# light-meter-B.net
KiCad netlist of a schematic drawn in EAGLE
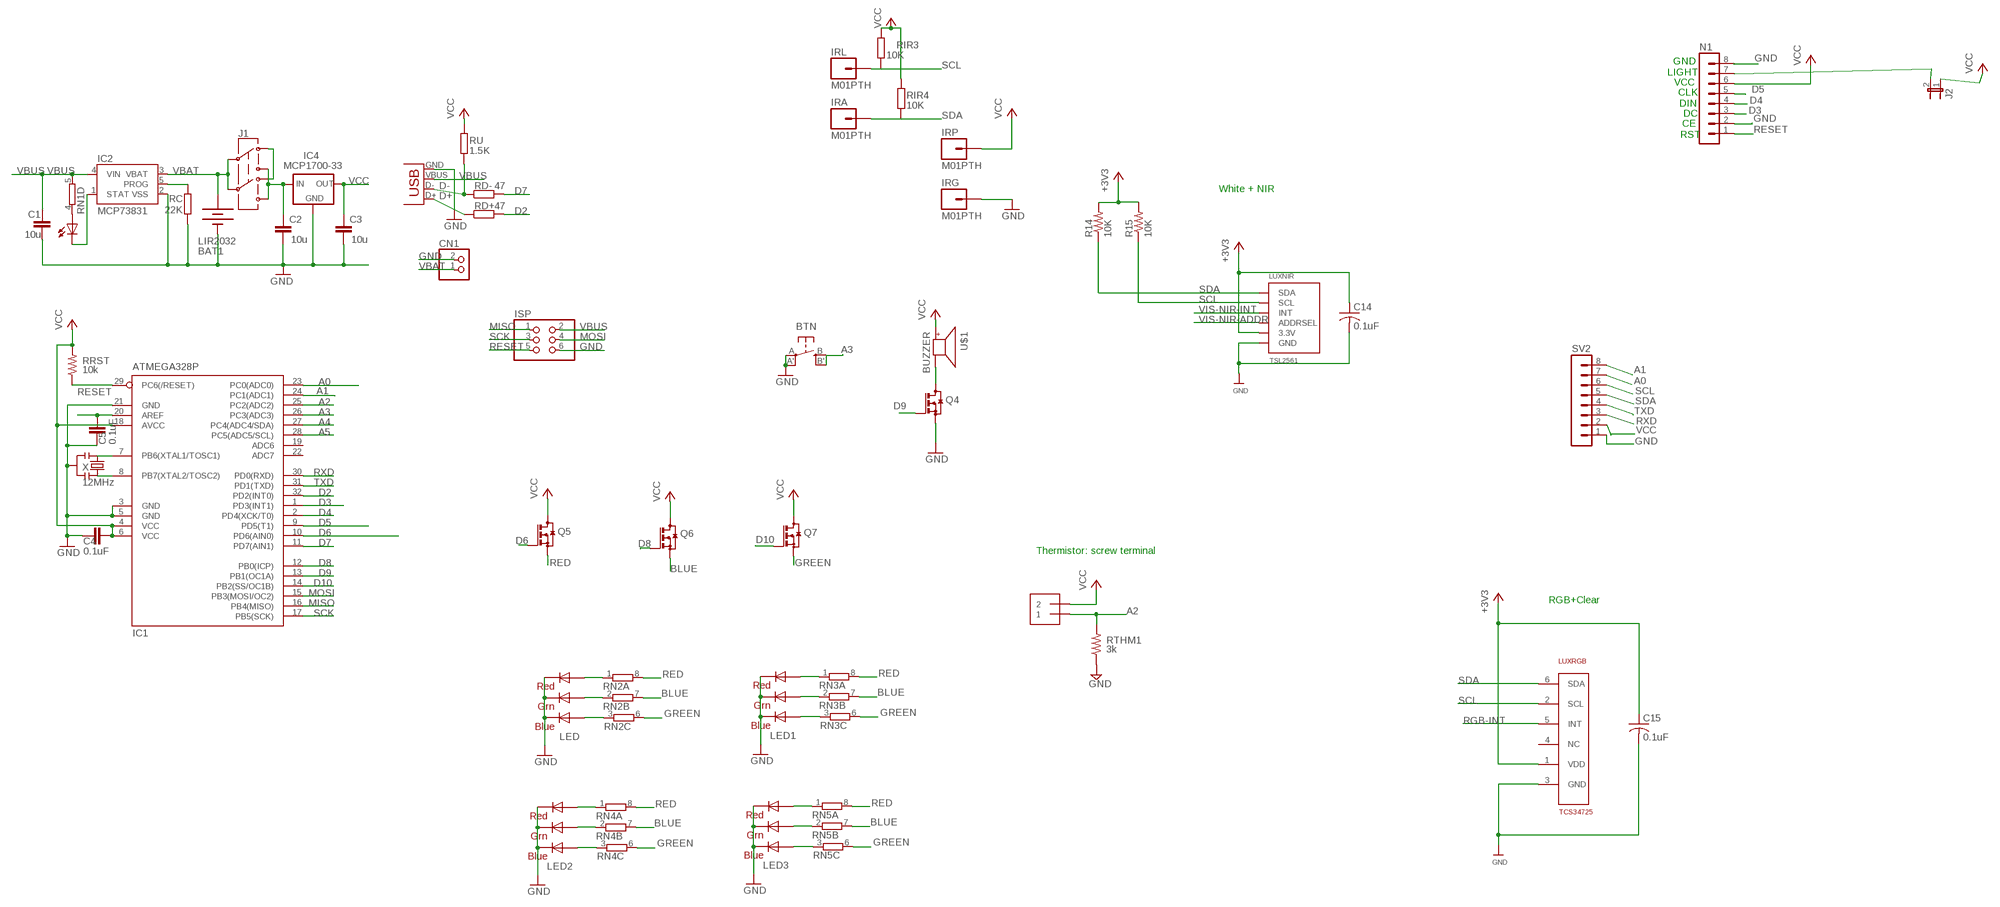
[diagram p0: schematic, sheet 1]

(export (version "E")
  (design (tool "Eeschema 10.0.6"))
  (components
    (comp (ref "BAT1")
      (value "LIR2032")
      (footprint "eagle-import:BATTCOM_20MM_PTH_SMT")
      (libsource (lib "eagle-import") (part "BATTERYBATTCOM_20MM_PTH_SMT"))
    )
    (comp (ref "BTN")
      (value "EVQQ2")
      (footprint "eagle-import:EVQ-Q2")
      (libsource (lib "eagle-import") (part "EVQQ2"))
    )
    (comp (ref "C1")
      (value "10u")
      (footprint "eagle-import:C0805")
      (libsource (lib "eagle-import") (part "resistor_C-EUC0805"))
    )
    (comp (ref "C2")
      (value "10u")
      (footprint "eagle-import:C0805")
      (libsource (lib "eagle-import") (part "resistor_C-EUC0805"))
    )
    (comp (ref "C3")
      (value "10u")
      (footprint "eagle-import:C0805")
      (libsource (lib "eagle-import") (part "resistor_C-EUC0805"))
    )
    (comp (ref "C4")
      (value "0.1uF")
      (footprint "eagle-import:C0805")
      (libsource (lib "eagle-import") (part "C-EUC0805"))
    )
    (comp (ref "C5")
      (value "0.1uF")
      (footprint "eagle-import:C0805")
      (libsource (lib "eagle-import") (part "C-EUC0805"))
    )
    (comp (ref "C14")
      (value "0.1uF")
      (footprint "eagle-import:C0805")
      (libsource (lib "eagle-import") (part "C-USC0805"))
    )
    (comp (ref "C15")
      (value "0.1uF")
      (footprint "eagle-import:C0805")
      (libsource (lib "eagle-import") (part "C-USC0805"))
    )
    (comp (ref "CHG")
      (value "0805")
      (footprint "eagle-import:CHIPLED_0805")
      (libsource (lib "eagle-import") (part "LEDCHIPLED_0805"))
    )
    (comp (ref "CN1")
      (value "JST_2PIN-SMT-RA")
      (footprint "eagle-import:JST-PH-2-SMT-RA")
      (libsource (lib "eagle-import") (part "JST_2PIN-SMT-RA"))
    )
    (comp (ref "IC1")
      (value "ATMEGA328P")
      (footprint "eagle-import:TQFP32-08")
      (fields (field (name "MPN") "ATMEGA8-16AU"))
      (libsource (lib "eagle-import") (part "MEGA8-AI"))
    )
    (comp (ref "IC2")
      (value "MCP73831")
      (footprint "eagle-import:SOT23-5")
      (libsource (lib "eagle-import") (part "MCP73831"))
    )
    (comp (ref "IC4")
      (value "MCP1700-33")
      (footprint "eagle-import:SOT23")
      (libsource (lib "eagle-import") (part "MCP1700SOT233"))
    )
    (comp (ref "IRA")
      (value "M01PTH")
      (footprint "eagle-import:1X01")
      (libsource (lib "eagle-import") (part "M01PTH"))
    )
    (comp (ref "IRG")
      (value "M01PTH")
      (footprint "eagle-import:1X01")
      (libsource (lib "eagle-import") (part "M01PTH"))
    )
    (comp (ref "IRL")
      (value "M01PTH")
      (footprint "eagle-import:1X01")
      (libsource (lib "eagle-import") (part "M01PTH"))
    )
    (comp (ref "IRP")
      (value "M01PTH")
      (footprint "eagle-import:1X01")
      (libsource (lib "eagle-import") (part "M01PTH"))
    )
    (comp (ref "ISP")
      (value "PINHD-2X3")
      (footprint "eagle-import:2X03")
      (libsource (lib "eagle-import") (part "PINHD-2X3"))
    )
    (comp (ref "J1")
      (value "AYZ0202")
      (footprint "eagle-import:AYZ0202")
      (libsource (lib "eagle-import") (part "AYZ0202"))
    )
    (comp (ref "J2")
      (value "JP1E")
      (footprint "eagle-import:JP1")
      (libsource (lib "eagle-import") (part "JP1E"))
    )
    (comp (ref "LED")
      (value "RGBLED5050")
      (footprint "eagle-import:RGBLED5050")
      (libsource (lib "eagle-import") (part "RGBLED5050"))
    )
    (comp (ref "LED1")
      (value "RGBLED5050")
      (footprint "eagle-import:RGBLED5050")
      (libsource (lib "eagle-import") (part "RGBLED5050"))
    )
    (comp (ref "LED2")
      (value "RGBLED5050")
      (footprint "eagle-import:RGBLED5050")
      (libsource (lib "eagle-import") (part "RGBLED5050"))
    )
    (comp (ref "LED3")
      (value "RGBLED5050")
      (footprint "eagle-import:RGBLED5050")
      (libsource (lib "eagle-import") (part "RGBLED5050"))
    )
    (comp (ref "LUXNIR")
      (value "TSL2561")
      (footprint "eagle-import:TSL2561_FN@1")
      (libsource (lib "eagle-import") (part "TSL2561"))
    )
    (comp (ref "LUXRGB")
      (value "TCS34725")
      (footprint "eagle-import:DFN-6")
      (libsource (lib "eagle-import") (part "TCS34725"))
    )
    (comp (ref "N1")
      (value "MA08-1")
      (footprint "eagle-import:MA08-1")
      (libsource (lib "eagle-import") (part "MA08-1"))
    )
    (comp (ref "Q4")
      (value "BSS123")
      (footprint "eagle-import:SOT23")
      (libsource (lib "eagle-import") (part "BSS123"))
    )
    (comp (ref "Q5")
      (value "BSS123")
      (footprint "eagle-import:SOT23")
      (libsource (lib "eagle-import") (part "BSS123"))
    )
    (comp (ref "Q6")
      (value "BSS123")
      (footprint "eagle-import:SOT23")
      (libsource (lib "eagle-import") (part "BSS123"))
    )
    (comp (ref "Q7")
      (value "BSS123")
      (footprint "eagle-import:SOT23")
      (libsource (lib "eagle-import") (part "BSS123"))
    )
    (comp (ref "R14")
      (value "10K")
      (footprint "eagle-import:R0805")
      (libsource (lib "eagle-import") (part "R-US_R0805"))
    )
    (comp (ref "R15")
      (value "10K")
      (footprint "eagle-import:R0805")
      (libsource (lib "eagle-import") (part "R-US_R0805"))
    )
    (comp (ref "RC")
      (value "22K")
      (footprint "eagle-import:R0805")
      (libsource (lib "eagle-import") (part "R-EU_R0805"))
    )
    (comp (ref "RD+")
      (value "47")
      (footprint "eagle-import:R0805")
      (libsource (lib "eagle-import") (part "R-EU_R0805"))
    )
    (comp (ref "RD-")
      (value "47")
      (footprint "eagle-import:R0805")
      (libsource (lib "eagle-import") (part "R-EU_R0805"))
    )
    (comp (ref "RIR3")
      (value "10K")
      (footprint "eagle-import:R0805")
      (libsource (lib "eagle-import") (part "R-EU_R0805"))
    )
    (comp (ref "RIR4")
      (value "10K")
      (footprint "eagle-import:R0805")
      (libsource (lib "eagle-import") (part "R-EU_R0805"))
    )
    (comp (ref "RN1")
      (value "4R-NEXB38V")
      (footprint "eagle-import:EXB38V")
      (libsource (lib "eagle-import") (part "4R-NEXB38V"))
    )
    (comp (ref "RN2")
      (value "4R-NEXB38V")
      (footprint "eagle-import:EXB38V")
      (libsource (lib "eagle-import") (part "4R-NEXB38V"))
    )
    (comp (ref "RN3")
      (value "4R-NEXB38V")
      (footprint "eagle-import:EXB38V")
      (libsource (lib "eagle-import") (part "4R-NEXB38V"))
    )
    (comp (ref "RN4")
      (value "4R-NEXB38V")
      (footprint "eagle-import:EXB38V")
      (libsource (lib "eagle-import") (part "4R-NEXB38V"))
    )
    (comp (ref "RN5")
      (value "4R-NEXB38V")
      (footprint "eagle-import:EXB38V")
      (libsource (lib "eagle-import") (part "4R-NEXB38V"))
    )
    (comp (ref "RRST")
      (value "10k")
      (footprint "eagle-import:R0805@1")
      (libsource (lib "eagle-import") (part "rcl_R-US_R0805"))
    )
    (comp (ref "RTHM1")
      (value "3k")
      (footprint "eagle-import:R0805@1")
      (libsource (lib "eagle-import") (part "rcl_R-US_R0805"))
    )
    (comp (ref "RU")
      (value "1.5K")
      (footprint "eagle-import:R0805")
      (libsource (lib "eagle-import") (part "R-EU_R0805"))
    )
    (comp (ref "SV2")
      (value "MA08-1")
      (footprint "eagle-import:MA08-1")
      (libsource (lib "eagle-import") (part "MA08-1"))
    )
    (comp (ref "THM1")
      (value "1X2-3.5MM")
      (footprint "eagle-import:1X2-3.5MM")
      (libsource (lib "eagle-import") (part "1X2-3.5MM"))
    )
    (comp (ref "U$1")
      (value "BUZZER")
      (footprint "eagle-import:SMT-8585-BUZZER")
      (libsource (lib "eagle-import") (part "BUZZER"))
    )
    (comp (ref "X")
      (value "12MHz")
      (footprint "eagle-import:RESONATOR-SMD")
      (libsource (lib "eagle-import") (part "RESONATORSMD"))
    )
    (comp (ref "X1")
      (value "USBSMD")
      (footprint "eagle-import:USB-MINIB")
      (libsource (lib "eagle-import") (part "USBSMD"))
    )
  )
  (nets
    (net (code "1") (name "+3V3") (class "Default")
      (node (ref "C14") (pin "1") (pinfunction "1_1") (pintype "passive"))
      (node (ref "C15") (pin "1") (pinfunction "1_1") (pintype "passive"))
      (node (ref "LUXNIR") (pin "VDD") (pinfunction "3.3V_VDD") (pintype "bidirectional"))
      (node (ref "LUXRGB") (pin "1") (pinfunction "VDD_1") (pintype "bidirectional"))
      (node (ref "R14") (pin "2") (pinfunction "2_2") (pintype "passive"))
      (node (ref "R15") (pin "2") (pinfunction "2_2") (pintype "passive"))
    )
    (net (code "2") (name "/A0") (class "Default")
      (node (ref "IC1") (pin "23") (pinfunction "PC0(ADC0)_23") (pintype "bidirectional"))
      (node (ref "SV2") (pin "7") (pinfunction "7_7") (pintype "passive"))
    )
    (net (code "3") (name "/A1") (class "Default")
      (node (ref "IC1") (pin "24") (pinfunction "PC1(ADC1)_24") (pintype "bidirectional"))
      (node (ref "SV2") (pin "8") (pinfunction "8_8") (pintype "passive"))
    )
    (net (code "4") (name "/A2") (class "Default")
      (node (ref "IC1") (pin "25") (pinfunction "PC2(ADC2)_25") (pintype "bidirectional"))
      (node (ref "RTHM1") (pin "2") (pinfunction "2_2") (pintype "passive"))
      (node (ref "THM1") (pin "1") (pinfunction "1_1") (pintype "passive"))
    )
    (net (code "5") (name "/A3") (class "Default")
      (node (ref "BTN") (pin "B") (pinfunction "S_B") (pintype "passive"))
      (node (ref "BTN") (pin "B'") (pinfunction "S1_B'") (pintype "passive"))
      (node (ref "IC1") (pin "26") (pinfunction "PC3(ADC3)_26") (pintype "bidirectional"))
    )
    (net (code "6") (name "/A4") (class "Default")
      (node (ref "IC1") (pin "27") (pinfunction "PC4(ADC4/SDA)_27") (pintype "bidirectional"))
    )
    (net (code "7") (name "/A5") (class "Default")
      (node (ref "IC1") (pin "28") (pinfunction "PC5(ADC5/SCL)_28") (pintype "bidirectional"))
    )
    (net (code "8") (name "/BLUE") (class "Default")
      (node (ref "Q6") (pin "2") (pinfunction "S_2") (pintype "passive"))
      (node (ref "RN2") (pin "7") (pinfunction "2_7") (pintype "passive"))
      (node (ref "RN3") (pin "7") (pinfunction "2_7") (pintype "passive"))
      (node (ref "RN4") (pin "7") (pinfunction "2_7") (pintype "passive"))
      (node (ref "RN5") (pin "7") (pinfunction "2_7") (pintype "passive"))
    )
    (net (code "9") (name "/D+") (class "Default")
      (node (ref "RD+") (pin "1") (pinfunction "1_1") (pintype "passive"))
      (node (ref "X1") (pin "D+") (pinfunction "D+_D+") (pintype "bidirectional"))
    )
    (net (code "10") (name "/D-") (class "Default")
      (node (ref "RD-") (pin "1") (pinfunction "1_1") (pintype "passive"))
      (node (ref "RU") (pin "1") (pinfunction "1_1") (pintype "passive"))
      (node (ref "X1") (pin "D-") (pinfunction "D-_D-") (pintype "bidirectional"))
    )
    (net (code "11") (name "/D2") (class "Default")
      (node (ref "IC1") (pin "32") (pinfunction "PD2(INT0)_32") (pintype "bidirectional"))
      (node (ref "RD+") (pin "2") (pinfunction "2_2") (pintype "passive"))
    )
    (net (code "12") (name "/D3") (class "Default")
      (node (ref "IC1") (pin "1") (pinfunction "PD3(INT1)_1") (pintype "bidirectional"))
      (node (ref "N1") (pin "3") (pinfunction "3_3") (pintype "passive"))
    )
    (net (code "13") (name "/D4") (class "Default")
      (node (ref "IC1") (pin "2") (pinfunction "PD4(XCK/T0)_2") (pintype "bidirectional"))
      (node (ref "N1") (pin "4") (pinfunction "4_4") (pintype "passive"))
    )
    (net (code "14") (name "/D5") (class "Default")
      (node (ref "IC1") (pin "9") (pinfunction "PD5(T1)_9") (pintype "bidirectional"))
      (node (ref "N1") (pin "5") (pinfunction "5_5") (pintype "passive"))
    )
    (net (code "15") (name "/D6") (class "Default")
      (node (ref "IC1") (pin "10") (pinfunction "PD6(AIN0)_10") (pintype "bidirectional"))
      (node (ref "Q5") (pin "1") (pinfunction "G_1") (pintype "passive"))
    )
    (net (code "16") (name "/D7") (class "Default")
      (node (ref "IC1") (pin "11") (pinfunction "PD7(AIN1)_11") (pintype "bidirectional"))
      (node (ref "RD-") (pin "2") (pinfunction "2_2") (pintype "passive"))
    )
    (net (code "17") (name "/D8") (class "Default")
      (node (ref "IC1") (pin "12") (pinfunction "PB0(ICP)_12") (pintype "bidirectional"))
      (node (ref "Q6") (pin "1") (pinfunction "G_1") (pintype "passive"))
    )
    (net (code "18") (name "/D9") (class "Default")
      (node (ref "IC1") (pin "13") (pinfunction "PB1(OC1A)_13") (pintype "bidirectional"))
      (node (ref "Q4") (pin "1") (pinfunction "G_1") (pintype "passive"))
    )
    (net (code "19") (name "/D10") (class "Default")
      (node (ref "IC1") (pin "14") (pinfunction "PB2(SS/OC1B)_14") (pintype "bidirectional"))
      (node (ref "Q7") (pin "1") (pinfunction "G_1") (pintype "passive"))
    )
    (net (code "20") (name "/GREEN") (class "Default")
      (node (ref "Q7") (pin "2") (pinfunction "S_2") (pintype "passive"))
      (node (ref "RN2") (pin "6") (pinfunction "2_6") (pintype "passive"))
      (node (ref "RN3") (pin "6") (pinfunction "2_6") (pintype "passive"))
      (node (ref "RN4") (pin "6") (pinfunction "2_6") (pintype "passive"))
      (node (ref "RN5") (pin "6") (pinfunction "2_6") (pintype "passive"))
    )
    (net (code "21") (name "/MISO") (class "Default")
      (node (ref "IC1") (pin "16") (pinfunction "PB4(MISO)_16") (pintype "bidirectional"))
      (node (ref "ISP") (pin "1") (pinfunction "1_1") (pintype "passive"))
    )
    (net (code "22") (name "/MOSI") (class "Default")
      (node (ref "IC1") (pin "15") (pinfunction "PB3(MOSI/OC2)_15") (pintype "bidirectional"))
      (node (ref "ISP") (pin "4") (pinfunction "4_4") (pintype "passive"))
    )
    (net (code "23") (name "/RED") (class "Default")
      (node (ref "Q5") (pin "2") (pinfunction "S_2") (pintype "passive"))
      (node (ref "RN2") (pin "8") (pinfunction "2_8") (pintype "passive"))
      (node (ref "RN3") (pin "8") (pinfunction "2_8") (pintype "passive"))
      (node (ref "RN4") (pin "8") (pinfunction "2_8") (pintype "passive"))
      (node (ref "RN5") (pin "8") (pinfunction "2_8") (pintype "passive"))
    )
    (net (code "24") (name "/RESET") (class "Default")
      (node (ref "IC1") (pin "29") (pinfunction "PC6(/RESET)_29") (pintype "bidirectional"))
      (node (ref "ISP") (pin "5") (pinfunction "5_5") (pintype "passive"))
      (node (ref "N1") (pin "1") (pinfunction "1_1") (pintype "passive"))
      (node (ref "RRST") (pin "1") (pinfunction "1_1") (pintype "passive"))
    )
    (net (code "25") (name "/RGB-INT") (class "Default")
      (node (ref "LUXRGB") (pin "5") (pinfunction "INT_5") (pintype "bidirectional"))
    )
    (net (code "26") (name "/RXD") (class "Default")
      (node (ref "IC1") (pin "30") (pinfunction "PD0(RXD)_30") (pintype "bidirectional"))
      (node (ref "SV2") (pin "3") (pinfunction "3_3") (pintype "passive"))
    )
    (net (code "27") (name "/SCK") (class "Default")
      (node (ref "IC1") (pin "17") (pinfunction "PB5(SCK)_17") (pintype "bidirectional"))
      (node (ref "ISP") (pin "3") (pinfunction "3_3") (pintype "passive"))
    )
    (net (code "28") (name "/SCL") (class "Default")
      (node (ref "IRL") (pin "1") (pinfunction "1_1") (pintype "passive"))
      (node (ref "LUXNIR") (pin "CLK") (pinfunction "SCL_CLK") (pintype "bidirectional"))
      (node (ref "LUXRGB") (pin "2") (pinfunction "SCL_2") (pintype "bidirectional"))
      (node (ref "R15") (pin "1") (pinfunction "1_1") (pintype "passive"))
      (node (ref "RIR3") (pin "1") (pinfunction "1_1") (pintype "passive"))
      (node (ref "SV2") (pin "6") (pinfunction "6_6") (pintype "passive"))
    )
    (net (code "29") (name "/SDA") (class "Default")
      (node (ref "IRA") (pin "1") (pinfunction "1_1") (pintype "passive"))
      (node (ref "LUXNIR") (pin "DATA") (pinfunction "SDA_DATA") (pintype "bidirectional"))
      (node (ref "LUXRGB") (pin "6") (pinfunction "SDA_6") (pintype "bidirectional"))
      (node (ref "R14") (pin "1") (pinfunction "1_1") (pintype "passive"))
      (node (ref "RIR4") (pin "1") (pinfunction "1_1") (pintype "passive"))
      (node (ref "SV2") (pin "5") (pinfunction "5_5") (pintype "passive"))
    )
    (net (code "30") (name "/TXD") (class "Default")
      (node (ref "IC1") (pin "31") (pinfunction "PD1(TXD)_31") (pintype "bidirectional"))
      (node (ref "SV2") (pin "4") (pinfunction "4_4") (pintype "passive"))
    )
    (net (code "31") (name "/VBAT") (class "Default")
      (node (ref "BAT1") (pin "P$2") (pinfunction "+_P$2") (pintype "power_in"))
      (node (ref "CN1") (pin "1") (pinfunction "2_1") (pintype "passive"))
      (node (ref "IC2") (pin "3") (pinfunction "VBAT_3") (pintype "power_in"))
      (node (ref "J1") (pin "2") (pinfunction "2_2") (pintype "bidirectional"))
      (node (ref "J1") (pin "5") (pinfunction "5_5") (pintype "bidirectional"))
    )
    (net (code "32") (name "/VBUS") (class "Default")
      (node (ref "C1") (pin "1") (pinfunction "1_1") (pintype "passive"))
      (node (ref "IC2") (pin "4") (pinfunction "VIN_4") (pintype "power_in"))
      (node (ref "ISP") (pin "2") (pinfunction "2_2") (pintype "passive"))
      (node (ref "RN1") (pin "5") (pinfunction "2_5") (pintype "passive"))
      (node (ref "X1") (pin "VBUS") (pinfunction "VBUS_VBUS") (pintype "bidirectional"))
    )
    (net (code "33") (name "/VIS-NIR-ADDR") (class "Default")
      (node (ref "LUXNIR") (pin "ADR") (pinfunction "ADDRSEL_ADR") (pintype "bidirectional"))
    )
    (net (code "34") (name "/VIS-NIR-INT") (class "Default")
      (node (ref "LUXNIR") (pin "INT") (pinfunction "INT_INT") (pintype "bidirectional"))
    )
    (net (code "35") (name "GND") (class "Default")
      (node (ref "BAT1") (pin "P$1") (pinfunction "-_P$1") (pintype "power_in"))
      (node (ref "BTN") (pin "A") (pinfunction "P_A") (pintype "passive"))
      (node (ref "BTN") (pin "A'") (pinfunction "P1_A'") (pintype "passive"))
      (node (ref "C1") (pin "2") (pinfunction "2_2") (pintype "passive"))
      (node (ref "C14") (pin "2") (pinfunction "2_2") (pintype "passive"))
      (node (ref "C15") (pin "2") (pinfunction "2_2") (pintype "passive"))
      (node (ref "C2") (pin "2") (pinfunction "2_2") (pintype "passive"))
      (node (ref "C3") (pin "2") (pinfunction "2_2") (pintype "passive"))
      (node (ref "C4") (pin "1") (pinfunction "1_1") (pintype "passive"))
      (node (ref "C5") (pin "1") (pinfunction "1_1") (pintype "passive"))
      (node (ref "CN1") (pin "2") (pinfunction "1_2") (pintype "passive"))
      (node (ref "IC1") (pin "21") (pinfunction "GND_21") (pintype "power_in"))
      (node (ref "IC1") (pin "3") (pinfunction "GND_3") (pintype "power_in"))
      (node (ref "IC1") (pin "5") (pinfunction "GND_5") (pintype "power_in"))
      (node (ref "IC2") (pin "2") (pinfunction "VSS_2") (pintype "power_in"))
      (node (ref "IC4") (pin "1") (pinfunction "GND_1") (pintype "input"))
      (node (ref "IRG") (pin "1") (pinfunction "1_1") (pintype "passive"))
      (node (ref "ISP") (pin "6") (pinfunction "6_6") (pintype "passive"))
      (node (ref "LED") (pin "4") (pinfunction "BLUE_C_4") (pintype "bidirectional"))
      (node (ref "LED") (pin "5") (pinfunction "RED_C_5") (pintype "bidirectional"))
      (node (ref "LED") (pin "6") (pinfunction "GREEN_C_6") (pintype "bidirectional"))
      (node (ref "LED1") (pin "4") (pinfunction "BLUE_C_4") (pintype "bidirectional"))
      (node (ref "LED1") (pin "5") (pinfunction "RED_C_5") (pintype "bidirectional"))
      (node (ref "LED1") (pin "6") (pinfunction "GREEN_C_6") (pintype "bidirectional"))
      (node (ref "LED2") (pin "4") (pinfunction "BLUE_C_4") (pintype "bidirectional"))
      (node (ref "LED2") (pin "5") (pinfunction "RED_C_5") (pintype "bidirectional"))
      (node (ref "LED2") (pin "6") (pinfunction "GREEN_C_6") (pintype "bidirectional"))
      (node (ref "LED3") (pin "4") (pinfunction "BLUE_C_4") (pintype "bidirectional"))
      (node (ref "LED3") (pin "5") (pinfunction "RED_C_5") (pintype "bidirectional"))
      (node (ref "LED3") (pin "6") (pinfunction "GREEN_C_6") (pintype "bidirectional"))
      (node (ref "LUXNIR") (pin "VSS") (pinfunction "GND_VSS") (pintype "bidirectional"))
      (node (ref "LUXRGB") (pin "3") (pinfunction "GND_3") (pintype "bidirectional"))
      (node (ref "N1") (pin "2") (pinfunction "2_2") (pintype "passive"))
      (node (ref "N1") (pin "8") (pinfunction "8_8") (pintype "passive"))
      (node (ref "Q4") (pin "2") (pinfunction "S_2") (pintype "passive"))
      (node (ref "RC") (pin "1") (pinfunction "1_1") (pintype "passive"))
      (node (ref "RTHM1") (pin "1") (pinfunction "1_1") (pintype "passive"))
      (node (ref "SV2") (pin "1") (pinfunction "1_1") (pintype "passive"))
      (node (ref "X") (pin "2") (pinfunction "2_2") (pintype "passive"))
      (node (ref "X1") (pin "GND") (pinfunction "GND_GND") (pintype "bidirectional"))
    )
    (net (code "36") (name "Net-(IC1-AREF)") (class "Default")
      (node (ref "C5") (pin "2") (pinfunction "2_2") (pintype "passive"))
      (node (ref "IC1") (pin "20") (pinfunction "AREF_20") (pintype "passive"))
    )
    (net (code "37") (name "Net-(IC1-PB6(XTAL1{slash}TOSC1))") (class "Default")
      (node (ref "IC1") (pin "7") (pinfunction "PB6(XTAL1/TOSC1)_7") (pintype "bidirectional"))
      (node (ref "X") (pin "1") (pinfunction "1_1") (pintype "passive"))
    )
    (net (code "38") (name "Net-(IC1-PB7(XTAL2{slash}TOSC2))") (class "Default")
      (node (ref "IC1") (pin "8") (pinfunction "PB7(XTAL2/TOSC2)_8") (pintype "bidirectional"))
      (node (ref "X") (pin "3") (pinfunction "3_3") (pintype "passive"))
    )
    (net (code "39") (name "Net-(IC2-PROG)") (class "Default")
      (node (ref "IC2") (pin "5") (pinfunction "PROG_5") (pintype "input"))
      (node (ref "RC") (pin "2") (pinfunction "2_2") (pintype "passive"))
    )
    (net (code "40") (name "Net-(IC2-STAT)") (class "Default")
      (node (ref "CHG") (pin "C") (pinfunction "C_C") (pintype "passive"))
      (node (ref "IC2") (pin "1") (pinfunction "STAT_1") (pintype "output"))
    )
    (net (code "41") (name "Net-(IC4-IN)") (class "Default")
      (node (ref "C2") (pin "1") (pinfunction "1_1") (pintype "passive"))
      (node (ref "IC4") (pin "3") (pinfunction "IN_3") (pintype "input"))
      (node (ref "J1") (pin "1") (pinfunction "3_1") (pintype "bidirectional"))
      (node (ref "J1") (pin "4") (pinfunction "6_4") (pintype "bidirectional"))
    )
    (net (code "42") (name "Net-(J1-1)") (class "Default")
      (node (ref "J1") (pin "3") (pinfunction "1_3") (pintype "bidirectional"))
      (node (ref "J1") (pin "6") (pinfunction "4_6") (pintype "bidirectional"))
    )
    (net (code "43") (name "Net-(J2-Pad2)") (class "Default")
      (node (ref "J2") (pin "2") (pinfunction "2_2") (pintype "passive"))
      (node (ref "N1") (pin "7") (pinfunction "7_7") (pintype "passive"))
    )
    (net (code "44") (name "Net-(LED-BLUE_A)") (class "Default")
      (node (ref "LED") (pin "3") (pinfunction "BLUE_A_3") (pintype "bidirectional"))
      (node (ref "RN2") (pin "3") (pinfunction "1_3") (pintype "passive"))
    )
    (net (code "45") (name "Net-(LED-GREEN_A)") (class "Default")
      (node (ref "LED") (pin "1") (pinfunction "GREEN_A_1") (pintype "bidirectional"))
      (node (ref "RN2") (pin "2") (pinfunction "1_2") (pintype "passive"))
    )
    (net (code "46") (name "Net-(LED-RED_A)") (class "Default")
      (node (ref "LED") (pin "2") (pinfunction "RED_A_2") (pintype "bidirectional"))
      (node (ref "RN2") (pin "1") (pinfunction "1_1") (pintype "passive"))
    )
    (net (code "47") (name "Net-(LED1-BLUE_A)") (class "Default")
      (node (ref "LED1") (pin "3") (pinfunction "BLUE_A_3") (pintype "bidirectional"))
      (node (ref "RN3") (pin "3") (pinfunction "1_3") (pintype "passive"))
    )
    (net (code "48") (name "Net-(LED1-GREEN_A)") (class "Default")
      (node (ref "LED1") (pin "1") (pinfunction "GREEN_A_1") (pintype "bidirectional"))
      (node (ref "RN3") (pin "2") (pinfunction "1_2") (pintype "passive"))
    )
    (net (code "49") (name "Net-(LED1-RED_A)") (class "Default")
      (node (ref "LED1") (pin "2") (pinfunction "RED_A_2") (pintype "bidirectional"))
      (node (ref "RN3") (pin "1") (pinfunction "1_1") (pintype "passive"))
    )
    (net (code "50") (name "Net-(LED2-BLUE_A)") (class "Default")
      (node (ref "LED2") (pin "3") (pinfunction "BLUE_A_3") (pintype "bidirectional"))
      (node (ref "RN4") (pin "3") (pinfunction "1_3") (pintype "passive"))
    )
    (net (code "51") (name "Net-(LED2-GREEN_A)") (class "Default")
      (node (ref "LED2") (pin "1") (pinfunction "GREEN_A_1") (pintype "bidirectional"))
      (node (ref "RN4") (pin "2") (pinfunction "1_2") (pintype "passive"))
    )
    (net (code "52") (name "Net-(LED2-RED_A)") (class "Default")
      (node (ref "LED2") (pin "2") (pinfunction "RED_A_2") (pintype "bidirectional"))
      (node (ref "RN4") (pin "1") (pinfunction "1_1") (pintype "passive"))
    )
    (net (code "53") (name "Net-(LED3-BLUE_A)") (class "Default")
      (node (ref "LED3") (pin "3") (pinfunction "BLUE_A_3") (pintype "bidirectional"))
      (node (ref "RN5") (pin "3") (pinfunction "1_3") (pintype "passive"))
    )
    (net (code "54") (name "Net-(LED3-GREEN_A)") (class "Default")
      (node (ref "LED3") (pin "1") (pinfunction "GREEN_A_1") (pintype "bidirectional"))
      (node (ref "RN5") (pin "2") (pinfunction "1_2") (pintype "passive"))
    )
    (net (code "55") (name "Net-(LED3-RED_A)") (class "Default")
      (node (ref "LED3") (pin "2") (pinfunction "RED_A_2") (pintype "bidirectional"))
      (node (ref "RN5") (pin "1") (pinfunction "1_1") (pintype "passive"))
    )
    (net (code "56") (name "Net-(Q4-D)") (class "Default")
      (node (ref "Q4") (pin "3") (pinfunction "D_3") (pintype "passive"))
      (node (ref "U$1") (pin "-") (pinfunction "-_-") (pintype "passive"))
    )
    (net (code "57") (name "Net-(RN1D-1)") (class "Default")
      (node (ref "CHG") (pin "A") (pinfunction "A_A") (pintype "passive"))
      (node (ref "RN1") (pin "4") (pinfunction "1_4") (pintype "passive"))
    )
    (net (code "58") (name "VCC") (class "Default")
      (node (ref "C3") (pin "1") (pinfunction "1_1") (pintype "passive"))
      (node (ref "C4") (pin "2") (pinfunction "2_2") (pintype "passive"))
      (node (ref "IC1") (pin "18") (pinfunction "AVCC_18") (pintype "power_in"))
      (node (ref "IC1") (pin "4") (pinfunction "VCC_4") (pintype "power_in"))
      (node (ref "IC1") (pin "6") (pinfunction "VCC_6") (pintype "power_in"))
      (node (ref "IC4") (pin "2") (pinfunction "OUT_2") (pintype "passive"))
      (node (ref "IRP") (pin "1") (pinfunction "1_1") (pintype "passive"))
      (node (ref "J2") (pin "1") (pinfunction "1_1") (pintype "passive"))
      (node (ref "N1") (pin "6") (pinfunction "6_6") (pintype "passive"))
      (node (ref "Q5") (pin "3") (pinfunction "D_3") (pintype "passive"))
      (node (ref "Q6") (pin "3") (pinfunction "D_3") (pintype "passive"))
      (node (ref "Q7") (pin "3") (pinfunction "D_3") (pintype "passive"))
      (node (ref "RIR3") (pin "2") (pinfunction "2_2") (pintype "passive"))
      (node (ref "RIR4") (pin "2") (pinfunction "2_2") (pintype "passive"))
      (node (ref "RRST") (pin "2") (pinfunction "2_2") (pintype "passive"))
      (node (ref "RU") (pin "2") (pinfunction "2_2") (pintype "passive"))
      (node (ref "SV2") (pin "2") (pinfunction "2_2") (pintype "passive"))
      (node (ref "THM1") (pin "2") (pinfunction "2_2") (pintype "passive"))
      (node (ref "U$1") (pin "+") (pinfunction "+_+") (pintype "passive"))
    )
    (net (code "59") (name "unconnected-(IC1-ADC6-Pad19)") (class "Default")
      (node (ref "IC1") (pin "19") (pinfunction "ADC6_19") (pintype "bidirectional"))
    )
    (net (code "60") (name "unconnected-(IC1-ADC7-Pad22)") (class "Default")
      (node (ref "IC1") (pin "22") (pinfunction "ADC7_22") (pintype "bidirectional"))
    )
    (net (code "61") (name "unconnected-(LUXRGB-NC-Pad4)") (class "Default")
      (node (ref "LUXRGB") (pin "4") (pinfunction "NC_4") (pintype "bidirectional"))
    )
  )
)
